# GCD_MiniMoto_v2.net
KiCad netlist of a schematic drawn in EAGLE
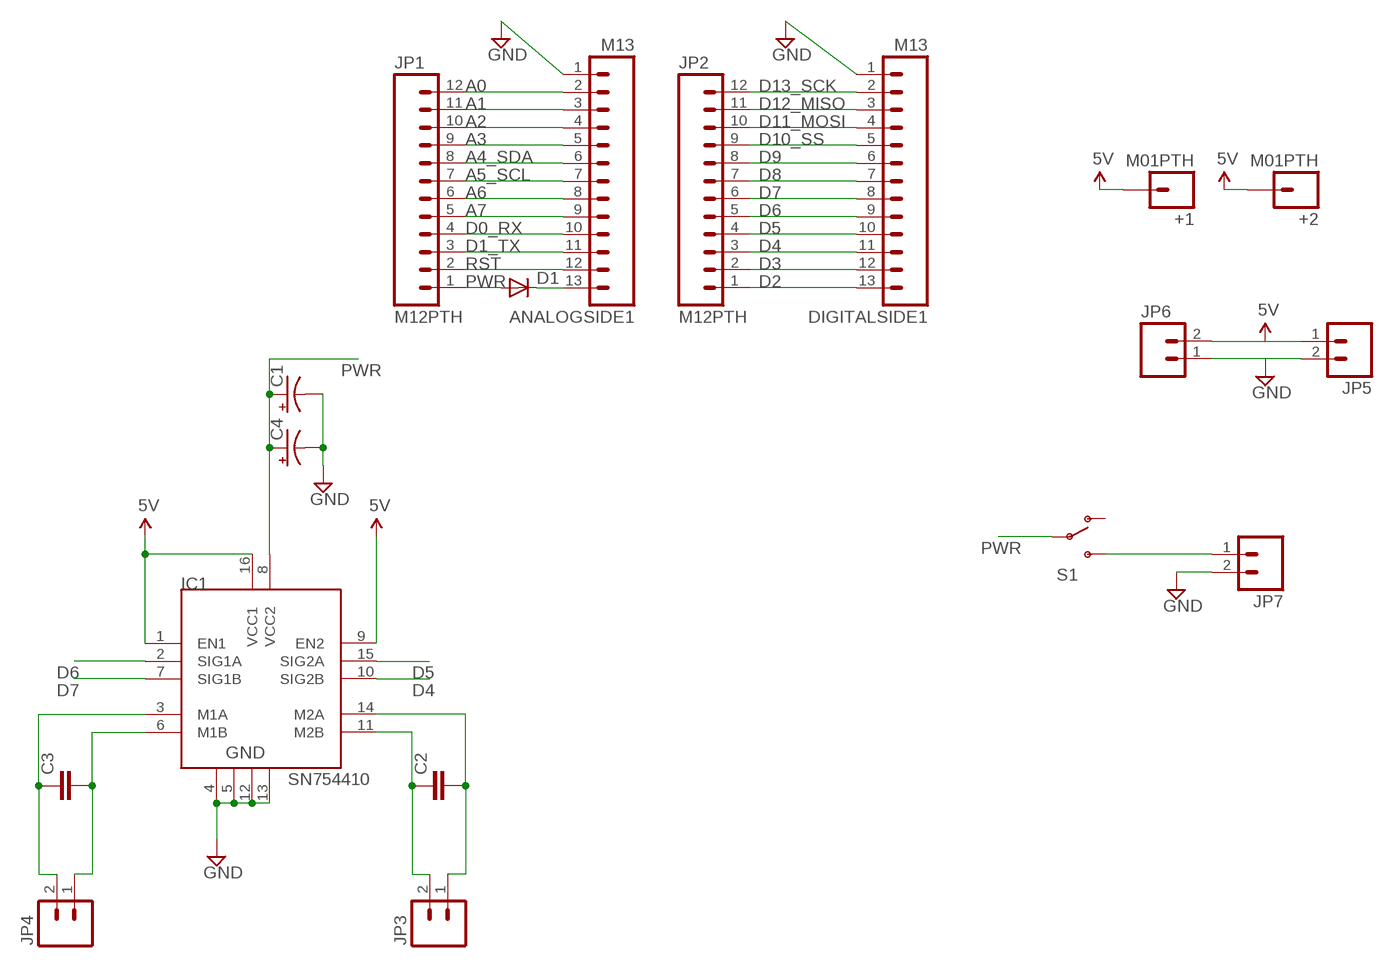
[diagram p0: schematic, sheet 1]

(export (version "E")
  (design (tool "Eeschema 10.0.6"))
  (components
    (comp (ref "+1")
      (value "M01PTH")
      (footprint "eagle-import:1X01")
      (libsource (lib "eagle-import") (part "M01PTH"))
    )
    (comp (ref "+2")
      (value "M01PTH")
      (footprint "eagle-import:1X01")
      (libsource (lib "eagle-import") (part "M01PTH"))
    )
    (comp (ref "ANALOGSIDE1")
      (value "M13")
      (footprint "eagle-import:1X13")
      (libsource (lib "eagle-import") (part "M13"))
    )
    (comp (ref "C1")
      (value "CAP_POLPTH1")
      (footprint "eagle-import:CPOL-RADIAL-100UF-25V")
      (libsource (lib "eagle-import") (part "CAP_POLPTH1"))
    )
    (comp (ref "C2")
      (value "CAPPTH1")
      (footprint "eagle-import:CAP-PTH-5MM")
      (libsource (lib "eagle-import") (part "CAPPTH1"))
    )
    (comp (ref "C3")
      (value "CAPPTH1")
      (footprint "eagle-import:CAP-PTH-5MM")
      (libsource (lib "eagle-import") (part "CAPPTH1"))
    )
    (comp (ref "C4")
      (value "CAP_POLPTH1")
      (footprint "eagle-import:CPOL-RADIAL-100UF-25V")
      (libsource (lib "eagle-import") (part "CAP_POLPTH1"))
    )
    (comp (ref "D1")
      (value "DIODESOD")
      (footprint "eagle-import:SOD-323")
      (libsource (lib "eagle-import") (part "DIODESOD"))
    )
    (comp (ref "DIGITALSIDE1")
      (value "M13")
      (footprint "eagle-import:1X13")
      (libsource (lib "eagle-import") (part "M13"))
    )
    (comp (ref "IC1")
      (value "SN754410")
      (footprint "eagle-import:DIP16")
      (libsource (lib "eagle-import") (part "SN754410"))
    )
    (comp (ref "JP1")
      (value "M12PTH")
      (footprint "eagle-import:1X12")
      (libsource (lib "eagle-import") (part "M12PTH"))
    )
    (comp (ref "JP2")
      (value "M12PTH")
      (footprint "eagle-import:1X12")
      (libsource (lib "eagle-import") (part "M12PTH"))
    )
    (comp (ref "JP3")
      (value "M025MM")
      (footprint "eagle-import:SCREWTERMINAL-5MM-2")
      (libsource (lib "eagle-import") (part "M025MM"))
    )
    (comp (ref "JP4")
      (value "M025MM")
      (footprint "eagle-import:SCREWTERMINAL-5MM-2")
      (libsource (lib "eagle-import") (part "M025MM"))
    )
    (comp (ref "JP5")
      (value "M02PTH")
      (footprint "eagle-import:1X02")
      (libsource (lib "eagle-import") (part "M02PTH"))
    )
    (comp (ref "JP6")
      (value "M02PTH")
      (footprint "eagle-import:1X02")
      (libsource (lib "eagle-import") (part "M02PTH"))
    )
    (comp (ref "JP7")
      (value "M02PTH")
      (footprint "eagle-import:1X02")
      (libsource (lib "eagle-import") (part "M02PTH"))
    )
    (comp (ref "S1")
      (value "SWITCH-SPDTPTH")
      (footprint "eagle-import:SWITCH-SPDT")
      (libsource (lib "eagle-import") (part "SWITCH-SPDTPTH"))
    )
  )
  (nets
    (net (code "1") (name "/A0") (class "Default")
      (node (ref "ANALOGSIDE1") (pin "2") (pinfunction "2_2") (pintype "passive"))
      (node (ref "JP1") (pin "12") (pinfunction "12_12") (pintype "passive"))
    )
    (net (code "2") (name "/A1") (class "Default")
      (node (ref "ANALOGSIDE1") (pin "3") (pinfunction "3_3") (pintype "passive"))
      (node (ref "JP1") (pin "11") (pinfunction "11_11") (pintype "passive"))
    )
    (net (code "3") (name "/A2") (class "Default")
      (node (ref "ANALOGSIDE1") (pin "4") (pinfunction "4_4") (pintype "passive"))
      (node (ref "JP1") (pin "10") (pinfunction "10_10") (pintype "passive"))
    )
    (net (code "4") (name "/A3") (class "Default")
      (node (ref "ANALOGSIDE1") (pin "5") (pinfunction "5_5") (pintype "passive"))
      (node (ref "JP1") (pin "9") (pinfunction "9_9") (pintype "passive"))
    )
    (net (code "5") (name "/A4_SDA") (class "Default")
      (node (ref "ANALOGSIDE1") (pin "6") (pinfunction "6_6") (pintype "passive"))
      (node (ref "JP1") (pin "8") (pinfunction "8_8") (pintype "passive"))
    )
    (net (code "6") (name "/A5_SCL") (class "Default")
      (node (ref "ANALOGSIDE1") (pin "7") (pinfunction "7_7") (pintype "passive"))
      (node (ref "JP1") (pin "7") (pinfunction "7_7") (pintype "passive"))
    )
    (net (code "7") (name "/A6") (class "Default")
      (node (ref "ANALOGSIDE1") (pin "8") (pinfunction "8_8") (pintype "passive"))
      (node (ref "JP1") (pin "6") (pinfunction "6_6") (pintype "passive"))
    )
    (net (code "8") (name "/A7") (class "Default")
      (node (ref "ANALOGSIDE1") (pin "9") (pinfunction "9_9") (pintype "passive"))
      (node (ref "JP1") (pin "5") (pinfunction "5_5") (pintype "passive"))
    )
    (net (code "9") (name "/D0_RX") (class "Default")
      (node (ref "ANALOGSIDE1") (pin "10") (pinfunction "10_10") (pintype "passive"))
      (node (ref "JP1") (pin "4") (pinfunction "4_4") (pintype "passive"))
    )
    (net (code "10") (name "/D1_TX") (class "Default")
      (node (ref "ANALOGSIDE1") (pin "11") (pinfunction "11_11") (pintype "passive"))
      (node (ref "JP1") (pin "3") (pinfunction "3_3") (pintype "passive"))
    )
    (net (code "11") (name "/D2") (class "Default")
      (node (ref "DIGITALSIDE1") (pin "13") (pinfunction "13_13") (pintype "passive"))
      (node (ref "JP2") (pin "1") (pinfunction "1_1") (pintype "passive"))
    )
    (net (code "12") (name "/D3") (class "Default")
      (node (ref "DIGITALSIDE1") (pin "12") (pinfunction "12_12") (pintype "passive"))
      (node (ref "JP2") (pin "2") (pinfunction "2_2") (pintype "passive"))
    )
    (net (code "13") (name "/D4") (class "Default")
      (node (ref "DIGITALSIDE1") (pin "11") (pinfunction "11_11") (pintype "passive"))
      (node (ref "IC1") (pin "10") (pinfunction "SIG2B_10") (pintype "bidirectional"))
      (node (ref "JP2") (pin "3") (pinfunction "3_3") (pintype "passive"))
    )
    (net (code "14") (name "/D5") (class "Default")
      (node (ref "DIGITALSIDE1") (pin "10") (pinfunction "10_10") (pintype "passive"))
      (node (ref "IC1") (pin "15") (pinfunction "SIG2A_15") (pintype "bidirectional"))
      (node (ref "JP2") (pin "4") (pinfunction "4_4") (pintype "passive"))
    )
    (net (code "15") (name "/D6") (class "Default")
      (node (ref "DIGITALSIDE1") (pin "9") (pinfunction "9_9") (pintype "passive"))
      (node (ref "IC1") (pin "2") (pinfunction "SIG1A_2") (pintype "bidirectional"))
      (node (ref "JP2") (pin "5") (pinfunction "5_5") (pintype "passive"))
    )
    (net (code "16") (name "/D7") (class "Default")
      (node (ref "DIGITALSIDE1") (pin "8") (pinfunction "8_8") (pintype "passive"))
      (node (ref "IC1") (pin "7") (pinfunction "SIG1B_7") (pintype "bidirectional"))
      (node (ref "JP2") (pin "6") (pinfunction "6_6") (pintype "passive"))
    )
    (net (code "17") (name "/D8") (class "Default")
      (node (ref "DIGITALSIDE1") (pin "7") (pinfunction "7_7") (pintype "passive"))
      (node (ref "JP2") (pin "7") (pinfunction "7_7") (pintype "passive"))
    )
    (net (code "18") (name "/D9") (class "Default")
      (node (ref "DIGITALSIDE1") (pin "6") (pinfunction "6_6") (pintype "passive"))
      (node (ref "JP2") (pin "8") (pinfunction "8_8") (pintype "passive"))
    )
    (net (code "19") (name "/D10_SS") (class "Default")
      (node (ref "DIGITALSIDE1") (pin "5") (pinfunction "5_5") (pintype "passive"))
      (node (ref "JP2") (pin "9") (pinfunction "9_9") (pintype "passive"))
    )
    (net (code "20") (name "/D11_MOSI") (class "Default")
      (node (ref "DIGITALSIDE1") (pin "4") (pinfunction "4_4") (pintype "passive"))
      (node (ref "JP2") (pin "10") (pinfunction "10_10") (pintype "passive"))
    )
    (net (code "21") (name "/D12_MISO") (class "Default")
      (node (ref "DIGITALSIDE1") (pin "3") (pinfunction "3_3") (pintype "passive"))
      (node (ref "JP2") (pin "11") (pinfunction "11_11") (pintype "passive"))
    )
    (net (code "22") (name "/D13_SCK") (class "Default")
      (node (ref "DIGITALSIDE1") (pin "2") (pinfunction "2_2") (pintype "passive"))
      (node (ref "JP2") (pin "12") (pinfunction "12_12") (pintype "passive"))
    )
    (net (code "23") (name "/PWR") (class "Default")
      (node (ref "C1") (pin "1") (pinfunction "+_1") (pintype "passive"))
      (node (ref "C4") (pin "1") (pinfunction "+_1") (pintype "passive"))
      (node (ref "D1") (pin "2") (pinfunction "A_2") (pintype "passive"))
      (node (ref "IC1") (pin "8") (pinfunction "VCC2_8") (pintype "power_in"))
      (node (ref "JP1") (pin "1") (pinfunction "1_1") (pintype "passive"))
      (node (ref "S1") (pin "2") (pinfunction "P_2") (pintype "passive"))
    )
    (net (code "24") (name "/RST") (class "Default")
      (node (ref "ANALOGSIDE1") (pin "12") (pinfunction "12_12") (pintype "passive"))
      (node (ref "JP1") (pin "2") (pinfunction "2_2") (pintype "passive"))
    )
    (net (code "25") (name "5V") (class "Default")
      (node (ref "+1") (pin "1") (pinfunction "1_1") (pintype "passive"))
      (node (ref "+2") (pin "1") (pinfunction "1_1") (pintype "passive"))
      (node (ref "IC1") (pin "1") (pinfunction "EN1_1") (pintype "bidirectional"))
      (node (ref "IC1") (pin "16") (pinfunction "VCC1_16") (pintype "power_in"))
      (node (ref "IC1") (pin "9") (pinfunction "EN2_9") (pintype "bidirectional"))
      (node (ref "JP5") (pin "1") (pinfunction "1_1") (pintype "passive"))
      (node (ref "JP6") (pin "2") (pinfunction "2_2") (pintype "passive"))
    )
    (net (code "26") (name "GND") (class "Default")
      (node (ref "ANALOGSIDE1") (pin "1") (pinfunction "1_1") (pintype "passive"))
      (node (ref "C1") (pin "2") (pinfunction "-_2") (pintype "passive"))
      (node (ref "C4") (pin "2") (pinfunction "-_2") (pintype "passive"))
      (node (ref "DIGITALSIDE1") (pin "1") (pinfunction "1_1") (pintype "passive"))
      (node (ref "IC1") (pin "12") (pinfunction "P12_12") (pintype "power_in"))
      (node (ref "IC1") (pin "13") (pinfunction "P13_13") (pintype "power_in"))
      (node (ref "IC1") (pin "4") (pinfunction "P4_4") (pintype "power_in"))
      (node (ref "IC1") (pin "5") (pinfunction "P5_5") (pintype "power_in"))
      (node (ref "JP5") (pin "2") (pinfunction "2_2") (pintype "passive"))
      (node (ref "JP6") (pin "1") (pinfunction "1_1") (pintype "passive"))
      (node (ref "JP7") (pin "2") (pinfunction "2_2") (pintype "passive"))
    )
    (net (code "27") (name "Net-(D1-C)") (class "Default")
      (node (ref "ANALOGSIDE1") (pin "13") (pinfunction "13_13") (pintype "passive"))
      (node (ref "D1") (pin "1") (pinfunction "C_1") (pintype "passive"))
    )
    (net (code "28") (name "Net-(IC1-M1A)") (class "Default")
      (node (ref "C3") (pin "1") (pinfunction "1_1") (pintype "passive"))
      (node (ref "IC1") (pin "3") (pinfunction "M1A_3") (pintype "bidirectional"))
      (node (ref "JP4") (pin "2") (pinfunction "2_2") (pintype "passive"))
    )
    (net (code "29") (name "Net-(IC1-M1B)") (class "Default")
      (node (ref "C3") (pin "2") (pinfunction "2_2") (pintype "passive"))
      (node (ref "IC1") (pin "6") (pinfunction "M1B_6") (pintype "bidirectional"))
      (node (ref "JP4") (pin "1") (pinfunction "1_1") (pintype "passive"))
    )
    (net (code "30") (name "Net-(IC1-M2A)") (class "Default")
      (node (ref "C2") (pin "2") (pinfunction "2_2") (pintype "passive"))
      (node (ref "IC1") (pin "14") (pinfunction "M2A_14") (pintype "bidirectional"))
      (node (ref "JP3") (pin "1") (pinfunction "1_1") (pintype "passive"))
    )
    (net (code "31") (name "Net-(IC1-M2B)") (class "Default")
      (node (ref "C2") (pin "1") (pinfunction "1_1") (pintype "passive"))
      (node (ref "IC1") (pin "11") (pinfunction "M2B_11") (pintype "bidirectional"))
      (node (ref "JP3") (pin "2") (pinfunction "2_2") (pintype "passive"))
    )
    (net (code "32") (name "Net-(S1-S)") (class "Default")
      (node (ref "JP7") (pin "1") (pinfunction "1_1") (pintype "passive"))
      (node (ref "S1") (pin "3") (pinfunction "S_3") (pintype "passive"))
    )
    (net (code "33") (name "unconnected-(S1-O-Pad1)") (class "Default")
      (node (ref "S1") (pin "1") (pinfunction "O_1") (pintype "passive"))
    )
  )
)
